# TSOC_NEOLED_R2_0.net
KiCad netlist of a schematic drawn in EAGLE
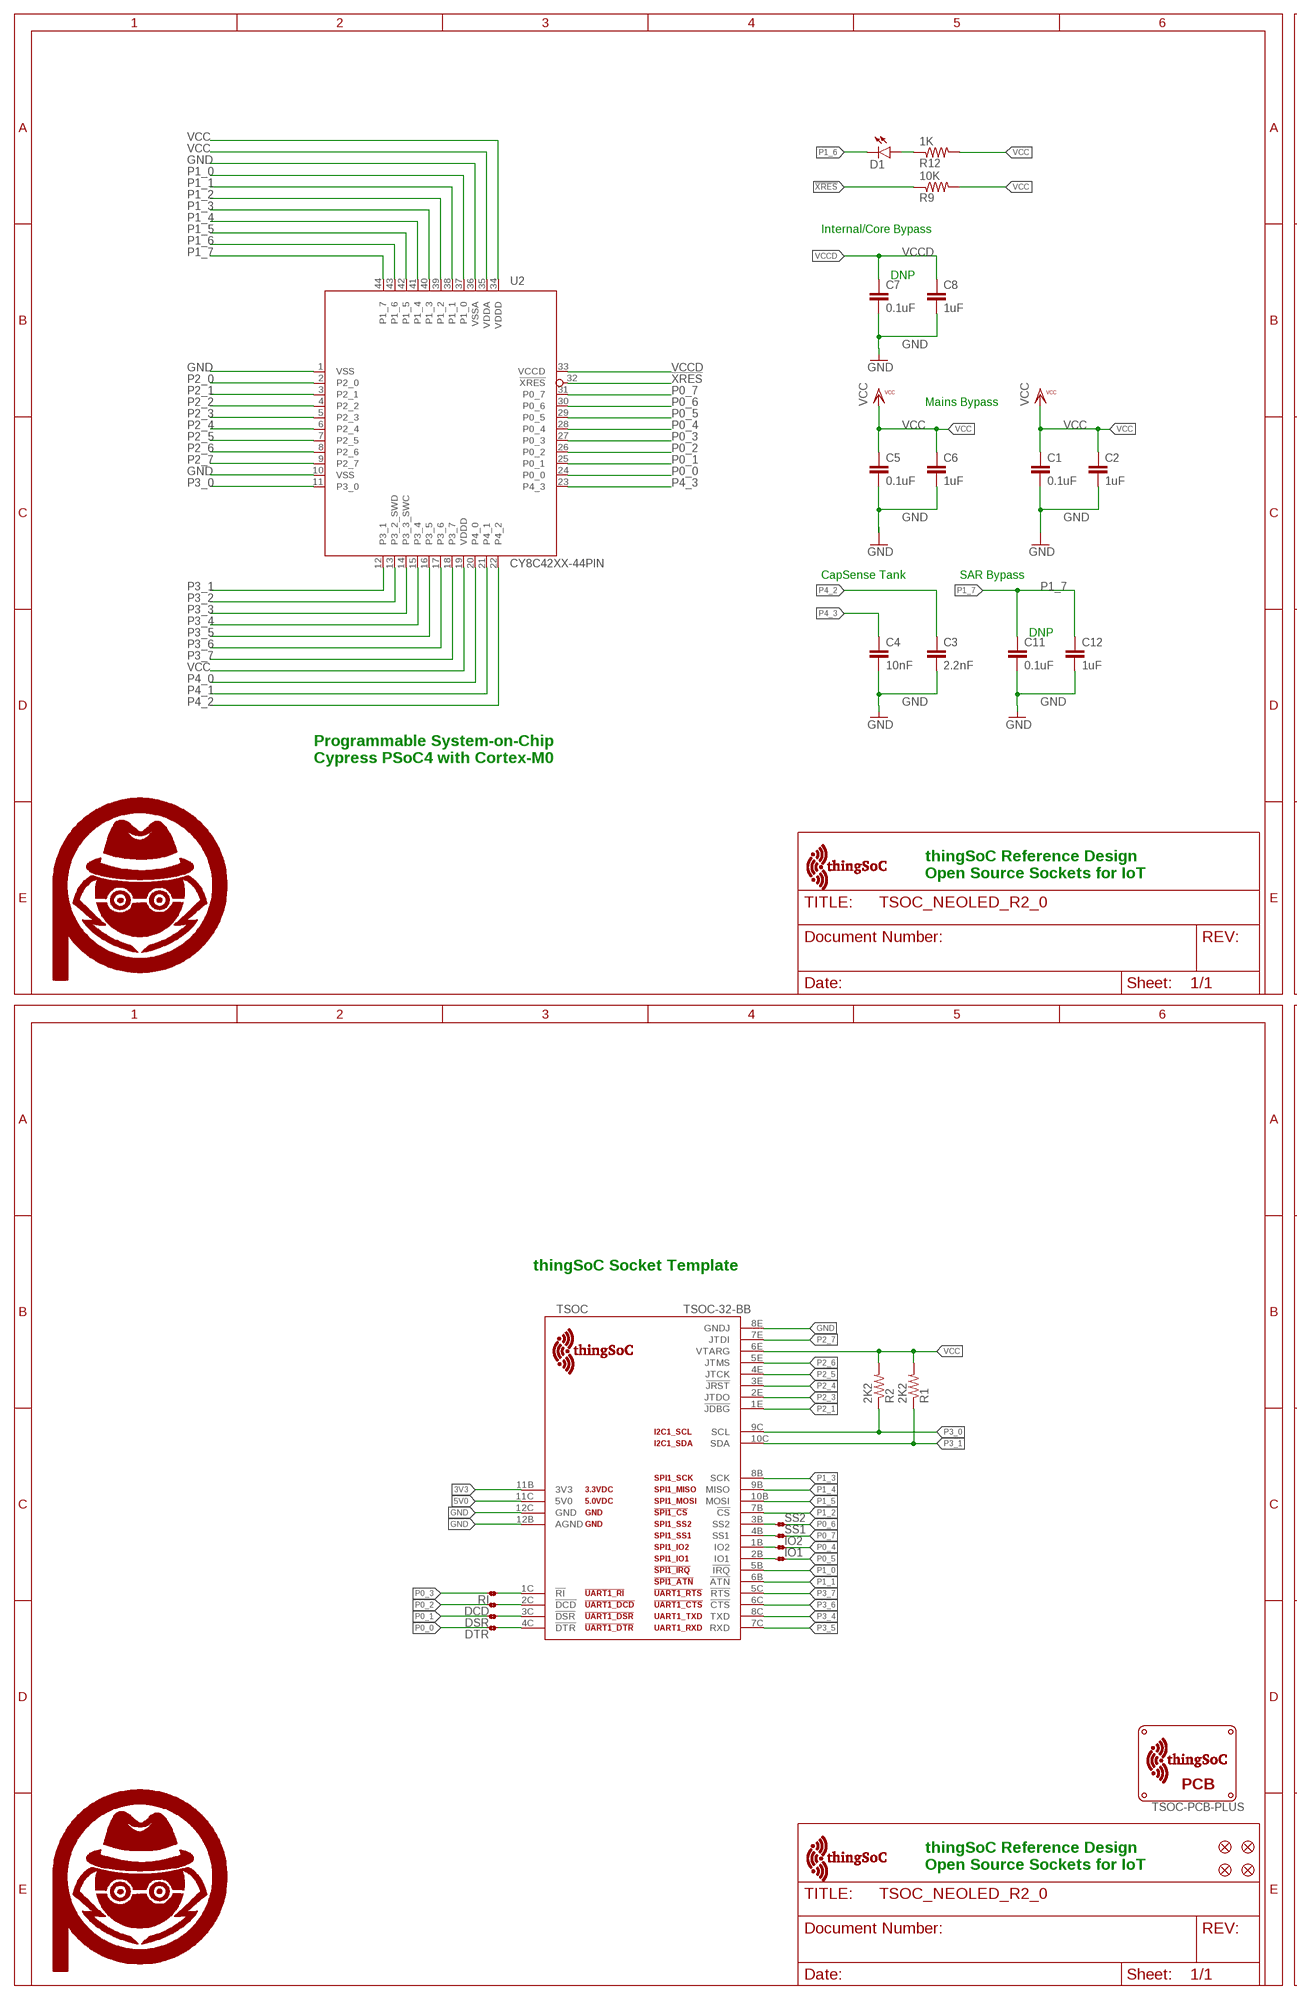
[diagram p0: schematic, sheet 1, part 1 of 2]
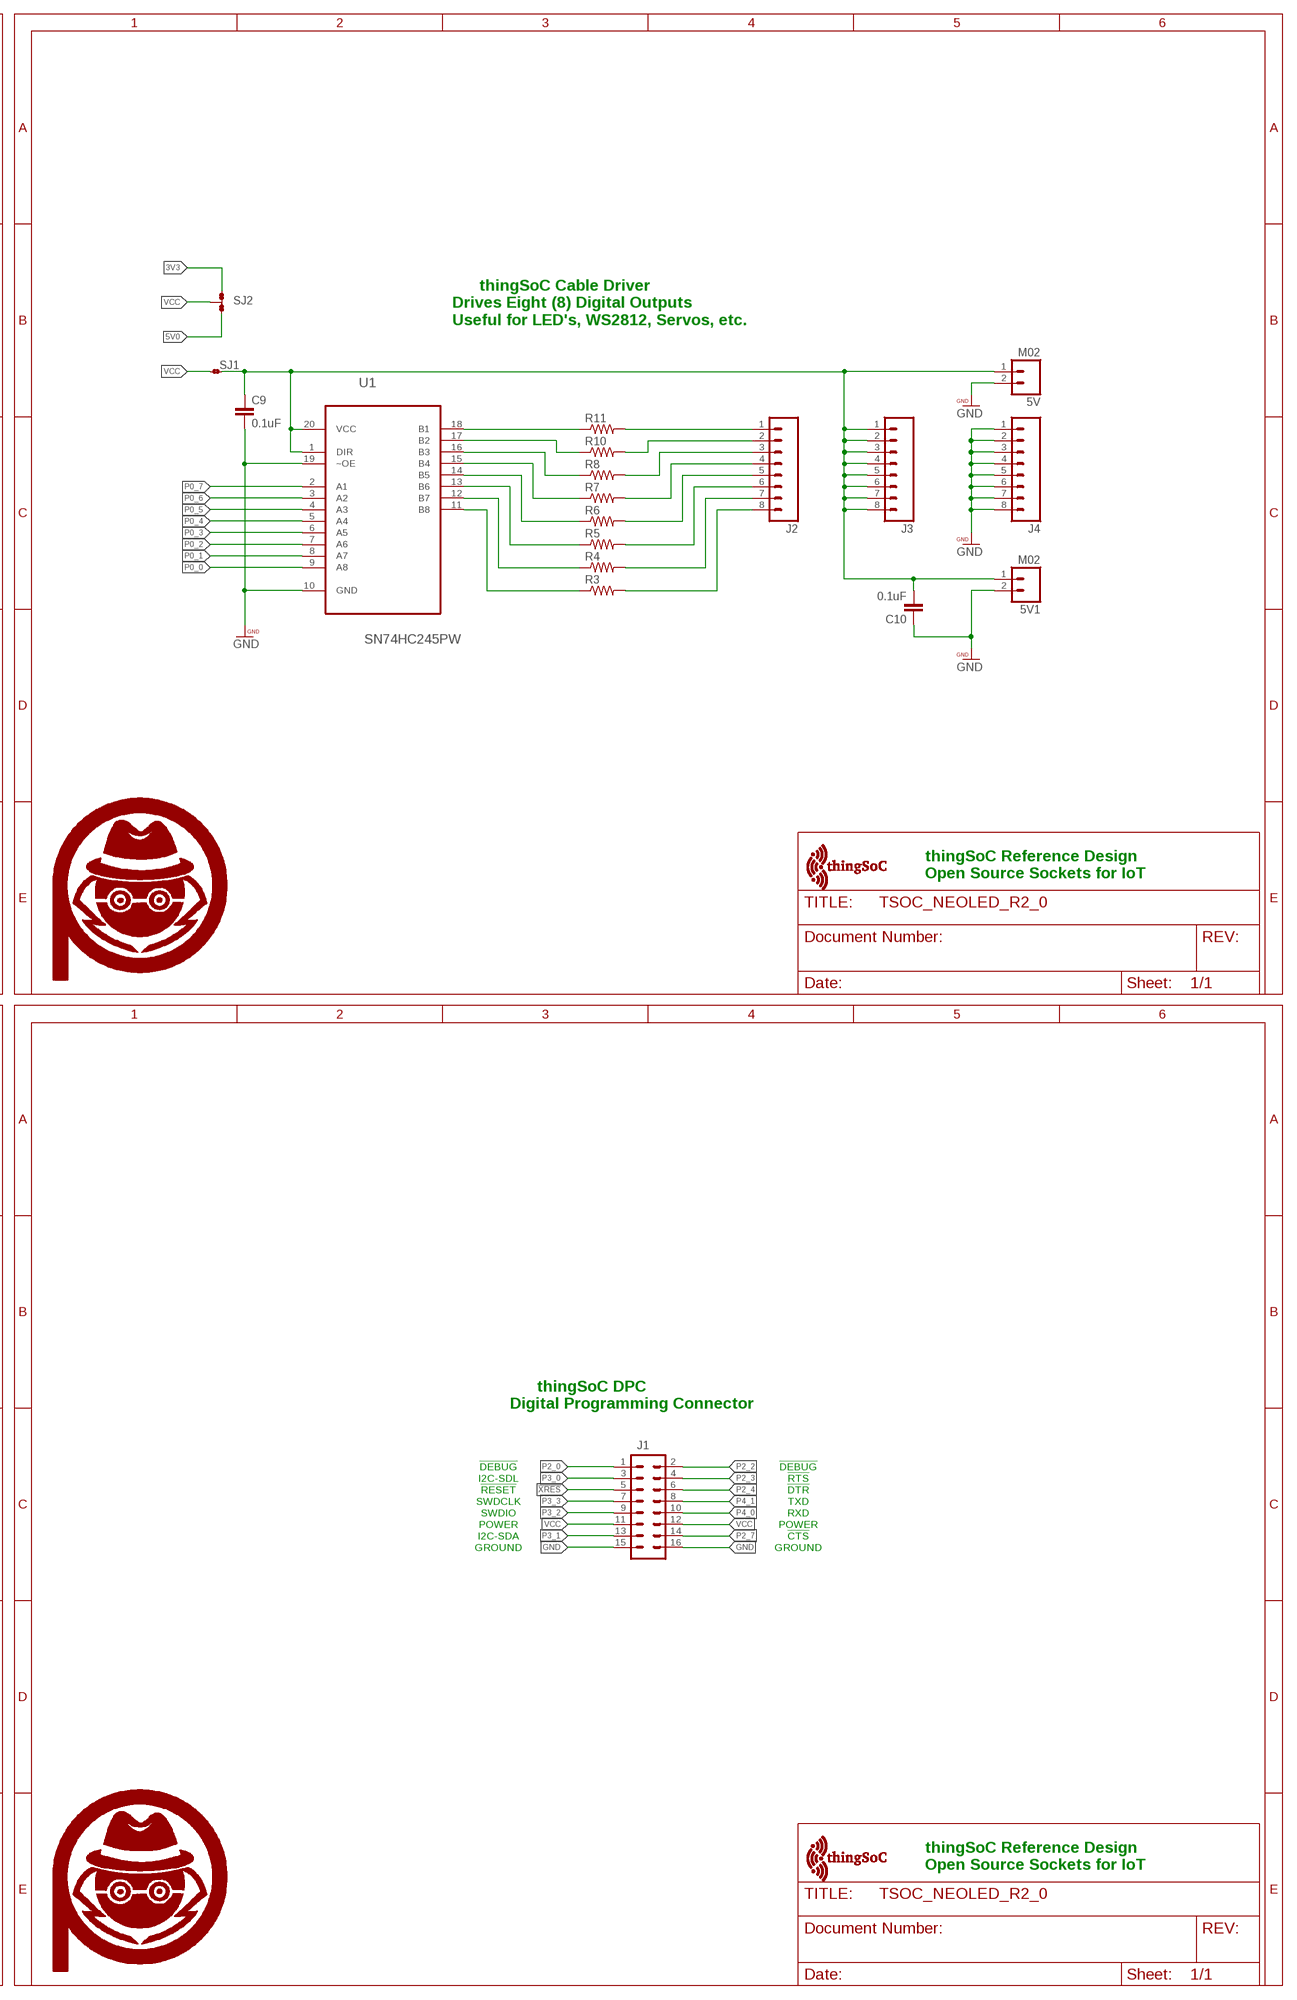
[diagram p1: schematic, sheet 1, part 2 of 2]

(export (version "E")
  (design (tool "Eeschema 10.0.6"))
  (components
    (comp (ref "$$U$1")
      (value "TSOC-LOGO-SMALL")
      (footprint "eagle-import:TSOC-LOGO-SML")
      (libsource (lib "eagle-import") (part "TSOC-LOGO-SMALL"))
    )
    (comp (ref "$$U$2")
      (value "TSOC-LOGO-MED")
      (footprint "eagle-import:TSOC-LOGO-MED")
      (libsource (lib "eagle-import") (part "TSOC-LOGO-MED"))
    )
    (comp (ref "5V")
      (value "M02")
      (footprint "eagle-import:1X02")
      (libsource (lib "eagle-import") (part "M02"))
    )
    (comp (ref "5V1")
      (value "M02")
      (footprint "eagle-import:1X02")
      (libsource (lib "eagle-import") (part "M02"))
    )
    (comp (ref "C1")
      (value "0.1uF")
      (footprint "eagle-import:0603-CAP")
      (libsource (lib "eagle-import") (part "CAP0603-CAP"))
    )
    (comp (ref "C2")
      (value "1uF")
      (footprint "eagle-import:0603-CAP")
      (libsource (lib "eagle-import") (part "CAP0603-CAP"))
    )
    (comp (ref "C3")
      (value "2.2nF")
      (footprint "eagle-import:0603-CAP")
      (libsource (lib "eagle-import") (part "CAP0603-CAP"))
    )
    (comp (ref "C4")
      (value "10nF")
      (footprint "eagle-import:0603-CAP")
      (libsource (lib "eagle-import") (part "CAP0603-CAP"))
    )
    (comp (ref "C5")
      (value "0.1uF")
      (footprint "eagle-import:0603-CAP")
      (libsource (lib "eagle-import") (part "CAP0603-CAP"))
    )
    (comp (ref "C6")
      (value "1uF")
      (footprint "eagle-import:0603-CAP")
      (libsource (lib "eagle-import") (part "CAP0603-CAP"))
    )
    (comp (ref "C7")
      (value "0.1uF")
      (footprint "eagle-import:0603-CAP")
      (libsource (lib "eagle-import") (part "CAP0603-CAP"))
    )
    (comp (ref "C8")
      (value "1uF")
      (footprint "eagle-import:0603-CAP")
      (libsource (lib "eagle-import") (part "CAP0603-CAP"))
    )
    (comp (ref "C9")
      (value "0.1uF")
      (footprint "eagle-import:0603-CAP")
      (libsource (lib "eagle-import") (part "CAP0603-CAP"))
    )
    (comp (ref "C10")
      (value "0.1uF")
      (footprint "eagle-import:0603-CAP")
      (libsource (lib "eagle-import") (part "CAP0603-CAP"))
    )
    (comp (ref "C11")
      (value "0.1uF")
      (footprint "eagle-import:0603-CAP")
      (libsource (lib "eagle-import") (part "CAP0603-CAP"))
    )
    (comp (ref "C12")
      (value "1uF")
      (footprint "eagle-import:0603-CAP")
      (libsource (lib "eagle-import") (part "CAP0603-CAP"))
    )
    (comp (ref "D1")
      (value "LED0603")
      (footprint "eagle-import:LED-0603")
      (libsource (lib "eagle-import") (part "LED0603"))
    )
    (comp (ref "DCD")
      (value "JMP-2-NO")
      (footprint "eagle-import:JMP-2-NO")
      (libsource (lib "eagle-import") (part "JMP-2-NO"))
    )
    (comp (ref "DSR")
      (value "JMP-2-NO")
      (footprint "eagle-import:JMP-2-NO")
      (libsource (lib "eagle-import") (part "JMP-2-NO"))
    )
    (comp (ref "DTR")
      (value "JMP-2-NO")
      (footprint "eagle-import:JMP-2-NO")
      (libsource (lib "eagle-import") (part "JMP-2-NO"))
    )
    (comp (ref "FID1")
      (value "FIDUCIALUFIDUCIAL")
      (footprint "eagle-import:MICRO-FIDUCIAL")
      (libsource (lib "eagle-import") (part "FIDUCIALUFIDUCIAL"))
    )
    (comp (ref "FID2")
      (value "FIDUCIALUFIDUCIAL")
      (footprint "eagle-import:MICRO-FIDUCIAL")
      (libsource (lib "eagle-import") (part "FIDUCIALUFIDUCIAL"))
    )
    (comp (ref "FID3")
      (value "FIDUCIALUFIDUCIAL")
      (footprint "eagle-import:MICRO-FIDUCIAL")
      (libsource (lib "eagle-import") (part "FIDUCIALUFIDUCIAL"))
    )
    (comp (ref "FID4")
      (value "FIDUCIALUFIDUCIAL")
      (footprint "eagle-import:MICRO-FIDUCIAL")
      (libsource (lib "eagle-import") (part "FIDUCIALUFIDUCIAL"))
    )
    (comp (ref "IO1")
      (value "JMP-2-NO")
      (footprint "eagle-import:JMP-2-NO")
      (libsource (lib "eagle-import") (part "JMP-2-NO"))
    )
    (comp (ref "IO2")
      (value "JMP-2-NO")
      (footprint "eagle-import:JMP-2-NO")
      (libsource (lib "eagle-import") (part "JMP-2-NO"))
    )
    (comp (ref "J1")
      (value "M08X2")
      (footprint "eagle-import:2X8")
      (libsource (lib "eagle-import") (part "M08X2"))
    )
    (comp (ref "J2")
      (value "M08")
      (footprint "eagle-import:1X08_ROUND")
      (libsource (lib "eagle-import") (part "M08"))
    )
    (comp (ref "J3")
      (value "M08")
      (footprint "eagle-import:1X08_ROUND")
      (libsource (lib "eagle-import") (part "M08"))
    )
    (comp (ref "J4")
      (value "M08")
      (footprint "eagle-import:1X08_ROUND")
      (libsource (lib "eagle-import") (part "M08"))
    )
    (comp (ref "R1")
      (value "2K2")
      (footprint "eagle-import:0603-RES")
      (libsource (lib "eagle-import") (part "RESISTOR_SFE0603-RES"))
    )
    (comp (ref "R2")
      (value "2K2")
      (footprint "eagle-import:0603-RES")
      (libsource (lib "eagle-import") (part "RESISTOR_SFE0603-RES"))
    )
    (comp (ref "R3")
      (value "RESISTOR0603-RES")
      (footprint "eagle-import:0603-RES")
      (libsource (lib "eagle-import") (part "RESISTOR0603-RES"))
    )
    (comp (ref "R4")
      (value "RESISTOR0603-RES")
      (footprint "eagle-import:0603-RES")
      (libsource (lib "eagle-import") (part "RESISTOR0603-RES"))
    )
    (comp (ref "R5")
      (value "RESISTOR0603-RES")
      (footprint "eagle-import:0603-RES")
      (libsource (lib "eagle-import") (part "RESISTOR0603-RES"))
    )
    (comp (ref "R6")
      (value "RESISTOR0603-RES")
      (footprint "eagle-import:0603-RES")
      (libsource (lib "eagle-import") (part "RESISTOR0603-RES"))
    )
    (comp (ref "R7")
      (value "RESISTOR0603-RES")
      (footprint "eagle-import:0603-RES")
      (libsource (lib "eagle-import") (part "RESISTOR0603-RES"))
    )
    (comp (ref "R8")
      (value "RESISTOR0603-RES")
      (footprint "eagle-import:0603-RES")
      (libsource (lib "eagle-import") (part "RESISTOR0603-RES"))
    )
    (comp (ref "R9")
      (value "10K")
      (footprint "eagle-import:0603-RES")
      (libsource (lib "eagle-import") (part "RESISTOR_SFE0603-RES"))
    )
    (comp (ref "R10")
      (value "RESISTOR0603-RES")
      (footprint "eagle-import:0603-RES")
      (libsource (lib "eagle-import") (part "RESISTOR0603-RES"))
    )
    (comp (ref "R11")
      (value "RESISTOR0603-RES")
      (footprint "eagle-import:0603-RES")
      (libsource (lib "eagle-import") (part "RESISTOR0603-RES"))
    )
    (comp (ref "R12")
      (value "1K")
      (footprint "eagle-import:0603-RES")
      (libsource (lib "eagle-import") (part "RESISTOR_SFE0603-RES"))
    )
    (comp (ref "RI")
      (value "JMP-2-NO")
      (footprint "eagle-import:JMP-2-NO")
      (libsource (lib "eagle-import") (part "JMP-2-NO"))
    )
    (comp (ref "SJ1")
      (value "JMP-2-NC")
      (footprint "eagle-import:JMP-2-NC")
      (libsource (lib "eagle-import") (part "JMP-2-NC"))
    )
    (comp (ref "SJ2")
      (value "JMP-3-NC")
      (footprint "eagle-import:JMP-3-NC")
      (libsource (lib "eagle-import") (part "JMP-3-NC"))
    )
    (comp (ref "SS1")
      (value "JMP-2-NO")
      (footprint "eagle-import:JMP-2-NO")
      (libsource (lib "eagle-import") (part "JMP-2-NO"))
    )
    (comp (ref "SS2")
      (value "JMP-2-NO")
      (footprint "eagle-import:JMP-2-NO")
      (libsource (lib "eagle-import") (part "JMP-2-NO"))
    )
    (comp (ref "TSOC")
      (value "TSOC-32-BB")
      (footprint "eagle-import:TSOC-BB-S32")
      (libsource (lib "eagle-import") (part "TSOC-32-BB"))
    )
    (comp (ref "U$1")
      (value "TSOC-PCB-PLUS")
      (footprint "eagle-import:TSOC-BB-BRD-PLUS")
      (libsource (lib "eagle-import") (part "TSOC-PCB-PLUS"))
    )
    (comp (ref "U$3")
      (value "PA_LOGO_SYMNULL")
      (footprint "eagle-import:NULL_SYM")
      (libsource (lib "eagle-import") (part "PA_LOGO_SYMNULL"))
    )
    (comp (ref "U$9")
      (value "PA_LOGO_SYMNULL")
      (footprint "eagle-import:NULL_SYM")
      (libsource (lib "eagle-import") (part "PA_LOGO_SYMNULL"))
    )
    (comp (ref "U$10")
      (value "PA_LOGO_SYMNULL")
      (footprint "eagle-import:NULL_SYM")
      (libsource (lib "eagle-import") (part "PA_LOGO_SYMNULL"))
    )
    (comp (ref "U$11")
      (value "PA_LOGO_SYMNULL")
      (footprint "eagle-import:NULL_SYM")
      (libsource (lib "eagle-import") (part "PA_LOGO_SYMNULL"))
    )
    (comp (ref "U$100")
      (value "TSOC-LOGO-SMALL")
      (footprint "eagle-import:TSOC-LOGO-SML")
      (libsource (lib "eagle-import") (part "TSOC-LOGO-SMALL"))
    )
    (comp (ref "U$101")
      (value "TSOC-LOGO-LRG")
      (footprint "eagle-import:TSOC-LOGO-LRG")
      (libsource (lib "eagle-import") (part "TSOC-LOGO-LRG"))
    )
    (comp (ref "U1")
      (value "SN74HC245PW")
      (footprint "eagle-import:SOP65P640X120-20N")
      (libsource (lib "eagle-import") (part "SN74HC245PW"))
    )
    (comp (ref "U2")
      (value "CY8C42XX-44PIN")
      (footprint "eagle-import:TQFP-10X10-44")
      (libsource (lib "eagle-import") (part "CY8C42XX-44PIN"))
    )
  )
  (nets
    (net (code "1") (name "/~{XRES}") (class "Default")
      (node (ref "J1") (pin "5") (pinfunction "5_5") (pintype "passive"))
      (node (ref "R9") (pin "1") (pinfunction "1_1") (pintype "passive"))
      (node (ref "U2") (pin "32") (pinfunction "~{XRES}_32") (pintype "bidirectional"))
    )
    (net (code "2") (name "3V3") (class "Default")
      (node (ref "SJ2") (pin "1") (pinfunction "1_1") (pintype "passive"))
      (node (ref "TSOC") (pin "11B") (pinfunction "3V3_11B") (pintype "bidirectional"))
    )
    (net (code "3") (name "5V0") (class "Default")
      (node (ref "SJ2") (pin "3") (pinfunction "3_3") (pintype "passive"))
      (node (ref "TSOC") (pin "11C") (pinfunction "5V0_11C") (pintype "bidirectional"))
    )
    (net (code "4") (name "GND") (class "Default")
      (node (ref "5V") (pin "2") (pinfunction "2_2") (pintype "passive"))
      (node (ref "5V1") (pin "2") (pinfunction "2_2") (pintype "passive"))
      (node (ref "C1") (pin "2") (pinfunction "2_2") (pintype "passive"))
      (node (ref "C10") (pin "1") (pinfunction "1_1") (pintype "passive"))
      (node (ref "C11") (pin "2") (pinfunction "2_2") (pintype "passive"))
      (node (ref "C12") (pin "2") (pinfunction "2_2") (pintype "passive"))
      (node (ref "C2") (pin "2") (pinfunction "2_2") (pintype "passive"))
      (node (ref "C3") (pin "2") (pinfunction "2_2") (pintype "passive"))
      (node (ref "C4") (pin "2") (pinfunction "2_2") (pintype "passive"))
      (node (ref "C5") (pin "2") (pinfunction "2_2") (pintype "passive"))
      (node (ref "C6") (pin "2") (pinfunction "2_2") (pintype "passive"))
      (node (ref "C7") (pin "2") (pinfunction "2_2") (pintype "passive"))
      (node (ref "C8") (pin "2") (pinfunction "2_2") (pintype "passive"))
      (node (ref "C9") (pin "2") (pinfunction "2_2") (pintype "passive"))
      (node (ref "J1") (pin "15") (pinfunction "15_15") (pintype "passive"))
      (node (ref "J1") (pin "16") (pinfunction "16_16") (pintype "passive"))
      (node (ref "J4") (pin "1") (pinfunction "1_1") (pintype "passive"))
      (node (ref "J4") (pin "2") (pinfunction "2_2") (pintype "passive"))
      (node (ref "J4") (pin "3") (pinfunction "3_3") (pintype "passive"))
      (node (ref "J4") (pin "4") (pinfunction "4_4") (pintype "passive"))
      (node (ref "J4") (pin "5") (pinfunction "5_5") (pintype "passive"))
      (node (ref "J4") (pin "6") (pinfunction "6_6") (pintype "passive"))
      (node (ref "J4") (pin "7") (pinfunction "7_7") (pintype "passive"))
      (node (ref "J4") (pin "8") (pinfunction "8_8") (pintype "passive"))
      (node (ref "TSOC") (pin "12B") (pinfunction "AGND_12B") (pintype "bidirectional"))
      (node (ref "TSOC") (pin "12C") (pinfunction "GND_12C") (pintype "bidirectional"))
      (node (ref "TSOC") (pin "8E") (pinfunction "GNDJ_8E") (pintype "bidirectional"))
      (node (ref "U1") (pin "10") (pinfunction "GND_10") (pintype "input"))
      (node (ref "U1") (pin "19") (pinfunction "~{OE}_19") (pintype "input"))
      (node (ref "U2") (pin "1") (pinfunction "VSS_1") (pintype "bidirectional"))
      (node (ref "U2") (pin "10") (pinfunction "VSS_10") (pintype "bidirectional"))
      (node (ref "U2") (pin "36") (pinfunction "VSSA_36") (pintype "bidirectional"))
    )
    (net (code "5") (name "Net-(D1-PadA)") (class "Default")
      (node (ref "D1") (pin "A") (pinfunction "A_A") (pintype "passive"))
      (node (ref "R12") (pin "1") (pinfunction "1_1") (pintype "passive"))
    )
    (net (code "6") (name "Net-(J2-Pad1)") (class "Default")
      (node (ref "J2") (pin "1") (pinfunction "1_1") (pintype "passive"))
      (node (ref "R11") (pin "2") (pinfunction "2_2") (pintype "passive"))
    )
    (net (code "7") (name "Net-(J2-Pad2)") (class "Default")
      (node (ref "J2") (pin "2") (pinfunction "2_2") (pintype "passive"))
      (node (ref "R10") (pin "2") (pinfunction "2_2") (pintype "passive"))
    )
    (net (code "8") (name "Net-(J2-Pad3)") (class "Default")
      (node (ref "J2") (pin "3") (pinfunction "3_3") (pintype "passive"))
      (node (ref "R8") (pin "2") (pinfunction "2_2") (pintype "passive"))
    )
    (net (code "9") (name "Net-(J2-Pad4)") (class "Default")
      (node (ref "J2") (pin "4") (pinfunction "4_4") (pintype "passive"))
      (node (ref "R7") (pin "2") (pinfunction "2_2") (pintype "passive"))
    )
    (net (code "10") (name "Net-(J2-Pad5)") (class "Default")
      (node (ref "J2") (pin "5") (pinfunction "5_5") (pintype "passive"))
      (node (ref "R6") (pin "2") (pinfunction "2_2") (pintype "passive"))
    )
    (net (code "11") (name "Net-(J2-Pad6)") (class "Default")
      (node (ref "J2") (pin "6") (pinfunction "6_6") (pintype "passive"))
      (node (ref "R5") (pin "2") (pinfunction "2_2") (pintype "passive"))
    )
    (net (code "12") (name "Net-(J2-Pad7)") (class "Default")
      (node (ref "J2") (pin "7") (pinfunction "7_7") (pintype "passive"))
      (node (ref "R4") (pin "2") (pinfunction "2_2") (pintype "passive"))
    )
    (net (code "13") (name "Net-(J2-Pad8)") (class "Default")
      (node (ref "J2") (pin "8") (pinfunction "8_8") (pintype "passive"))
      (node (ref "R3") (pin "2") (pinfunction "2_2") (pintype "passive"))
    )
    (net (code "14") (name "Net-(TSOC-IO1)") (class "Default")
      (node (ref "IO1") (pin "1") (pinfunction "1_1") (pintype "passive"))
      (node (ref "TSOC") (pin "2B") (pinfunction "IO1_2B") (pintype "bidirectional"))
    )
    (net (code "15") (name "Net-(TSOC-IO2)") (class "Default")
      (node (ref "IO2") (pin "1") (pinfunction "1_1") (pintype "passive"))
      (node (ref "TSOC") (pin "1B") (pinfunction "IO2_1B") (pintype "bidirectional"))
    )
    (net (code "16") (name "Net-(TSOC-SS1)") (class "Default")
      (node (ref "SS1") (pin "1") (pinfunction "1_1") (pintype "passive"))
      (node (ref "TSOC") (pin "4B") (pinfunction "SS1_4B") (pintype "bidirectional"))
    )
    (net (code "17") (name "Net-(TSOC-SS2)") (class "Default")
      (node (ref "SS2") (pin "1") (pinfunction "1_1") (pintype "passive"))
      (node (ref "TSOC") (pin "3B") (pinfunction "SS2_3B") (pintype "bidirectional"))
    )
    (net (code "18") (name "Net-(TSOC-~{DCD})") (class "Default")
      (node (ref "DCD") (pin "1") (pinfunction "1_1") (pintype "passive"))
      (node (ref "TSOC") (pin "2C") (pinfunction "~{DCD}_2C") (pintype "bidirectional"))
    )
    (net (code "19") (name "Net-(TSOC-~{DSR})") (class "Default")
      (node (ref "DSR") (pin "1") (pinfunction "1_1") (pintype "passive"))
      (node (ref "TSOC") (pin "3C") (pinfunction "~{DSR}_3C") (pintype "bidirectional"))
    )
    (net (code "20") (name "Net-(TSOC-~{DTR})") (class "Default")
      (node (ref "DTR") (pin "1") (pinfunction "1_1") (pintype "passive"))
      (node (ref "TSOC") (pin "4C") (pinfunction "~{DTR}_4C") (pintype "bidirectional"))
    )
    (net (code "21") (name "Net-(TSOC-~{RI})") (class "Default")
      (node (ref "RI") (pin "1") (pinfunction "1_1") (pintype "passive"))
      (node (ref "TSOC") (pin "1C") (pinfunction "~{RI}_1C") (pintype "bidirectional"))
    )
    (net (code "22") (name "Net-(U1-B1)") (class "Default")
      (node (ref "R11") (pin "1") (pinfunction "1_1") (pintype "passive"))
      (node (ref "U1") (pin "18") (pinfunction "B1_18") (pintype "bidirectional"))
    )
    (net (code "23") (name "Net-(U1-B2)") (class "Default")
      (node (ref "R10") (pin "1") (pinfunction "1_1") (pintype "passive"))
      (node (ref "U1") (pin "17") (pinfunction "B2_17") (pintype "bidirectional"))
    )
    (net (code "24") (name "Net-(U1-B3)") (class "Default")
      (node (ref "R8") (pin "1") (pinfunction "1_1") (pintype "passive"))
      (node (ref "U1") (pin "16") (pinfunction "B3_16") (pintype "bidirectional"))
    )
    (net (code "25") (name "Net-(U1-B4)") (class "Default")
      (node (ref "R7") (pin "1") (pinfunction "1_1") (pintype "passive"))
      (node (ref "U1") (pin "15") (pinfunction "B4_15") (pintype "bidirectional"))
    )
    (net (code "26") (name "Net-(U1-B5)") (class "Default")
      (node (ref "R6") (pin "1") (pinfunction "1_1") (pintype "passive"))
      (node (ref "U1") (pin "14") (pinfunction "B5_14") (pintype "bidirectional"))
    )
    (net (code "27") (name "Net-(U1-B6)") (class "Default")
      (node (ref "R5") (pin "1") (pinfunction "1_1") (pintype "passive"))
      (node (ref "U1") (pin "13") (pinfunction "B6_13") (pintype "bidirectional"))
    )
    (net (code "28") (name "Net-(U1-B7)") (class "Default")
      (node (ref "R4") (pin "1") (pinfunction "1_1") (pintype "passive"))
      (node (ref "U1") (pin "12") (pinfunction "B7_12") (pintype "bidirectional"))
    )
    (net (code "29") (name "Net-(U1-B8)") (class "Default")
      (node (ref "R3") (pin "1") (pinfunction "1_1") (pintype "passive"))
      (node (ref "U1") (pin "11") (pinfunction "B8_11") (pintype "bidirectional"))
    )
    (net (code "30") (name "Net-(U1-DIR)") (class "Default")
      (node (ref "5V") (pin "1") (pinfunction "1_1") (pintype "passive"))
      (node (ref "5V1") (pin "1") (pinfunction "1_1") (pintype "passive"))
      (node (ref "C10") (pin "2") (pinfunction "2_2") (pintype "passive"))
      (node (ref "C9") (pin "1") (pinfunction "1_1") (pintype "passive"))
      (node (ref "J3") (pin "1") (pinfunction "1_1") (pintype "passive"))
      (node (ref "J3") (pin "2") (pinfunction "2_2") (pintype "passive"))
      (node (ref "J3") (pin "3") (pinfunction "3_3") (pintype "passive"))
      (node (ref "J3") (pin "4") (pinfunction "4_4") (pintype "passive"))
      (node (ref "J3") (pin "5") (pinfunction "5_5") (pintype "passive"))
      (node (ref "J3") (pin "6") (pinfunction "6_6") (pintype "passive"))
      (node (ref "J3") (pin "7") (pinfunction "7_7") (pintype "passive"))
      (node (ref "J3") (pin "8") (pinfunction "8_8") (pintype "passive"))
      (node (ref "SJ1") (pin "2") (pinfunction "2_2") (pintype "passive"))
      (node (ref "U1") (pin "1") (pinfunction "DIR_1") (pintype "input"))
      (node (ref "U1") (pin "20") (pinfunction "VCC_20") (pintype "power_in"))
    )
    (net (code "31") (name "P0_0") (class "Default")
      (node (ref "DTR") (pin "2") (pinfunction "2_2") (pintype "passive"))
      (node (ref "U1") (pin "9") (pinfunction "A8_9") (pintype "bidirectional"))
      (node (ref "U2") (pin "24") (pinfunction "P0_0_24") (pintype "bidirectional"))
    )
    (net (code "32") (name "P0_1") (class "Default")
      (node (ref "DSR") (pin "2") (pinfunction "2_2") (pintype "passive"))
      (node (ref "U1") (pin "8") (pinfunction "A7_8") (pintype "bidirectional"))
      (node (ref "U2") (pin "25") (pinfunction "P0_1_25") (pintype "bidirectional"))
    )
    (net (code "33") (name "P0_2") (class "Default")
      (node (ref "DCD") (pin "2") (pinfunction "2_2") (pintype "passive"))
      (node (ref "U1") (pin "7") (pinfunction "A6_7") (pintype "bidirectional"))
      (node (ref "U2") (pin "26") (pinfunction "P0_2_26") (pintype "input"))
    )
    (net (code "34") (name "P0_3") (class "Default")
      (node (ref "RI") (pin "2") (pinfunction "2_2") (pintype "passive"))
      (node (ref "U1") (pin "6") (pinfunction "A5_6") (pintype "bidirectional"))
      (node (ref "U2") (pin "27") (pinfunction "P0_3_27") (pintype "bidirectional"))
    )
    (net (code "35") (name "P0_4") (class "Default")
      (node (ref "IO2") (pin "2") (pinfunction "2_2") (pintype "passive"))
      (node (ref "U1") (pin "5") (pinfunction "A4_5") (pintype "bidirectional"))
      (node (ref "U2") (pin "28") (pinfunction "P0_4_28") (pintype "bidirectional"))
    )
    (net (code "36") (name "P0_5") (class "Default")
      (node (ref "IO1") (pin "2") (pinfunction "2_2") (pintype "passive"))
      (node (ref "U1") (pin "4") (pinfunction "A3_4") (pintype "bidirectional"))
      (node (ref "U2") (pin "29") (pinfunction "P0_5_29") (pintype "bidirectional"))
    )
    (net (code "37") (name "P0_6") (class "Default")
      (node (ref "SS2") (pin "2") (pinfunction "2_2") (pintype "passive"))
      (node (ref "U1") (pin "3") (pinfunction "A2_3") (pintype "bidirectional"))
      (node (ref "U2") (pin "30") (pinfunction "P0_6_30") (pintype "power_in"))
    )
    (net (code "38") (name "P0_7") (class "Default")
      (node (ref "SS1") (pin "2") (pinfunction "2_2") (pintype "passive"))
      (node (ref "U1") (pin "2") (pinfunction "A1_2") (pintype "bidirectional"))
      (node (ref "U2") (pin "31") (pinfunction "P0_7_31") (pintype "bidirectional"))
    )
    (net (code "39") (name "P1_0") (class "Default")
      (node (ref "TSOC") (pin "5B") (pinfunction "~{IRQ}_5B") (pintype "bidirectional"))
      (node (ref "U2") (pin "37") (pinfunction "P1_0_37") (pintype "bidirectional"))
    )
    (net (code "40") (name "P1_1") (class "Default")
      (node (ref "TSOC") (pin "6B") (pinfunction "~{ATN}_6B") (pintype "bidirectional"))
      (node (ref "U2") (pin "38") (pinfunction "P1_1_38") (pintype "bidirectional"))
    )
    (net (code "41") (name "P1_2") (class "Default")
      (node (ref "TSOC") (pin "7B") (pinfunction "~{CS}_7B") (pintype "bidirectional"))
      (node (ref "U2") (pin "39") (pinfunction "P1_2_39") (pintype "power_in"))
    )
    (net (code "42") (name "P1_3") (class "Default")
      (node (ref "TSOC") (pin "8B") (pinfunction "SCK_8B") (pintype "bidirectional"))
      (node (ref "U2") (pin "40") (pinfunction "P1_3_40") (pintype "bidirectional"))
    )
    (net (code "43") (name "P1_4") (class "Default")
      (node (ref "TSOC") (pin "9B") (pinfunction "MISO_9B") (pintype "bidirectional"))
      (node (ref "U2") (pin "41") (pinfunction "P1_4_41") (pintype "bidirectional"))
    )
    (net (code "44") (name "P1_5") (class "Default")
      (node (ref "TSOC") (pin "10B") (pinfunction "MOSI_10B") (pintype "bidirectional"))
      (node (ref "U2") (pin "42") (pinfunction "P1_5_42") (pintype "bidirectional"))
    )
    (net (code "45") (name "P1_6") (class "Default")
      (node (ref "D1") (pin "C") (pinfunction "C_C") (pintype "passive"))
      (node (ref "U2") (pin "43") (pinfunction "P1_6_43") (pintype "bidirectional"))
    )
    (net (code "46") (name "P1_7") (class "Default")
      (node (ref "C11") (pin "1") (pinfunction "1_1") (pintype "passive"))
      (node (ref "C12") (pin "1") (pinfunction "1_1") (pintype "passive"))
      (node (ref "U2") (pin "44") (pinfunction "P1_7_44") (pintype "bidirectional"))
    )
    (net (code "47") (name "P2_0") (class "Default")
      (node (ref "J1") (pin "1") (pinfunction "1_1") (pintype "passive"))
      (node (ref "U2") (pin "2") (pinfunction "P2_0_2") (pintype "bidirectional"))
    )
    (net (code "48") (name "P2_1") (class "Default")
      (node (ref "TSOC") (pin "1E") (pinfunction "~{JDBG}_1E") (pintype "bidirectional"))
      (node (ref "U2") (pin "3") (pinfunction "P2_1_3") (pintype "bidirectional"))
    )
    (net (code "49") (name "P2_2") (class "Default")
      (node (ref "J1") (pin "2") (pinfunction "2_2") (pintype "passive"))
      (node (ref "U2") (pin "4") (pinfunction "P2_2_4") (pintype "power_in"))
    )
    (net (code "50") (name "P2_3") (class "Default")
      (node (ref "J1") (pin "4") (pinfunction "4_4") (pintype "passive"))
      (node (ref "TSOC") (pin "2E") (pinfunction "JTDO_2E") (pintype "bidirectional"))
      (node (ref "U2") (pin "5") (pinfunction "P2_3_5") (pintype "bidirectional"))
    )
    (net (code "51") (name "P2_4") (class "Default")
      (node (ref "J1") (pin "6") (pinfunction "6_6") (pintype "passive"))
      (node (ref "TSOC") (pin "3E") (pinfunction "~{JRST}_3E") (pintype "bidirectional"))
      (node (ref "U2") (pin "6") (pinfunction "P2_4_6") (pintype "bidirectional"))
    )
    (net (code "52") (name "P2_5") (class "Default")
      (node (ref "TSOC") (pin "4E") (pinfunction "JTCK_4E") (pintype "bidirectional"))
      (node (ref "U2") (pin "7") (pinfunction "P2_5_7") (pintype "bidirectional"))
    )
    (net (code "53") (name "P2_6") (class "Default")
      (node (ref "TSOC") (pin "5E") (pinfunction "JTMS_5E") (pintype "bidirectional"))
      (node (ref "U2") (pin "8") (pinfunction "P2_6_8") (pintype "power_in"))
    )
    (net (code "54") (name "P2_7") (class "Default")
      (node (ref "J1") (pin "14") (pinfunction "14_14") (pintype "passive"))
      (node (ref "TSOC") (pin "7E") (pinfunction "JTDI_7E") (pintype "bidirectional"))
      (node (ref "U2") (pin "9") (pinfunction "P2_7_9") (pintype "bidirectional"))
    )
    (net (code "55") (name "P3_0") (class "Default")
      (node (ref "J1") (pin "3") (pinfunction "3_3") (pintype "passive"))
      (node (ref "R2") (pin "1") (pinfunction "1_1") (pintype "passive"))
      (node (ref "TSOC") (pin "9C") (pinfunction "SCL_9C") (pintype "bidirectional"))
      (node (ref "U2") (pin "11") (pinfunction "P3_0_11") (pintype "bidirectional"))
    )
    (net (code "56") (name "P3_1") (class "Default")
      (node (ref "J1") (pin "13") (pinfunction "13_13") (pintype "passive"))
      (node (ref "R1") (pin "1") (pinfunction "1_1") (pintype "passive"))
      (node (ref "TSOC") (pin "10C") (pinfunction "SDA_10C") (pintype "bidirectional"))
      (node (ref "U2") (pin "12") (pinfunction "P3_1_12") (pintype "bidirectional"))
    )
    (net (code "57") (name "P3_2") (class "Default")
      (node (ref "J1") (pin "9") (pinfunction "9_9") (pintype "passive"))
      (node (ref "U2") (pin "13") (pinfunction "P3_2_SWD_13") (pintype "bidirectional"))
    )
    (net (code "58") (name "P3_3") (class "Default")
      (node (ref "J1") (pin "7") (pinfunction "7_7") (pintype "passive"))
      (node (ref "U2") (pin "14") (pinfunction "P3_3_SWC_14") (pintype "bidirectional"))
    )
    (net (code "59") (name "P3_4") (class "Default")
      (node (ref "TSOC") (pin "8C") (pinfunction "TXD_8C") (pintype "bidirectional"))
      (node (ref "U2") (pin "15") (pinfunction "P3_4_15") (pintype "bidirectional"))
    )
    (net (code "60") (name "P3_5") (class "Default")
      (node (ref "TSOC") (pin "7C") (pinfunction "RXD_7C") (pintype "bidirectional"))
      (node (ref "U2") (pin "16") (pinfunction "P3_5_16") (pintype "bidirectional"))
    )
    (net (code "61") (name "P3_6") (class "Default")
      (node (ref "TSOC") (pin "6C") (pinfunction "~{CTS}_6C") (pintype "bidirectional"))
      (node (ref "U2") (pin "17") (pinfunction "P3_6_17") (pintype "power_in"))
    )
    (net (code "62") (name "P3_7") (class "Default")
      (node (ref "TSOC") (pin "5C") (pinfunction "~{RTS}_5C") (pintype "bidirectional"))
      (node (ref "U2") (pin "18") (pinfunction "P3_7_18") (pintype "bidirectional"))
    )
    (net (code "63") (name "P4_0") (class "Default")
      (node (ref "J1") (pin "10") (pinfunction "10_10") (pintype "passive"))
      (node (ref "U2") (pin "20") (pinfunction "P4_0_20") (pintype "bidirectional"))
    )
    (net (code "64") (name "P4_1") (class "Default")
      (node (ref "J1") (pin "8") (pinfunction "8_8") (pintype "passive"))
      (node (ref "U2") (pin "21") (pinfunction "P4_1_21") (pintype "bidirectional"))
    )
    (net (code "65") (name "P4_2") (class "Default")
      (node (ref "C3") (pin "1") (pinfunction "1_1") (pintype "passive"))
      (node (ref "U2") (pin "22") (pinfunction "P4_2_22") (pintype "bidirectional"))
    )
    (net (code "66") (name "P4_3") (class "Default")
      (node (ref "C4") (pin "1") (pinfunction "1_1") (pintype "passive"))
      (node (ref "U2") (pin "23") (pinfunction "P4_3_23") (pintype "bidirectional"))
    )
    (net (code "67") (name "VCC") (class "Default")
      (node (ref "C1") (pin "1") (pinfunction "1_1") (pintype "passive"))
      (node (ref "C2") (pin "1") (pinfunction "1_1") (pintype "passive"))
      (node (ref "C5") (pin "1") (pinfunction "1_1") (pintype "passive"))
      (node (ref "C6") (pin "1") (pinfunction "1_1") (pintype "passive"))
      (node (ref "J1") (pin "11") (pinfunction "11_11") (pintype "passive"))
      (node (ref "J1") (pin "12") (pinfunction "12_12") (pintype "passive"))
      (node (ref "R1") (pin "2") (pinfunction "2_2") (pintype "passive"))
      (node (ref "R12") (pin "2") (pinfunction "2_2") (pintype "passive"))
      (node (ref "R2") (pin "2") (pinfunction "2_2") (pintype "passive"))
      (node (ref "R9") (pin "2") (pinfunction "2_2") (pintype "passive"))
      (node (ref "SJ1") (pin "1") (pinfunction "1_1") (pintype "passive"))
      (node (ref "SJ2") (pin "2") (pinfunction "2_2") (pintype "passive"))
      (node (ref "TSOC") (pin "6E") (pinfunction "VTARG_6E") (pintype "bidirectional"))
      (node (ref "U2") (pin "19") (pinfunction "VDDD_19") (pintype "bidirectional"))
      (node (ref "U2") (pin "34") (pinfunction "VDDD_34") (pintype "bidirectional"))
      (node (ref "U2") (pin "35") (pinfunction "VDDA_35") (pintype "bidirectional"))
    )
    (net (code "68") (name "VCCD") (class "Default")
      (node (ref "C7") (pin "1") (pinfunction "1_1") (pintype "passive"))
      (node (ref "C8") (pin "1") (pinfunction "1_1") (pintype "passive"))
      (node (ref "U2") (pin "33") (pinfunction "VCCD_33") (pintype "bidirectional"))
    )
  )
)
